# Ethernet.net
KiCad netlist of a schematic drawn in Altium Designer
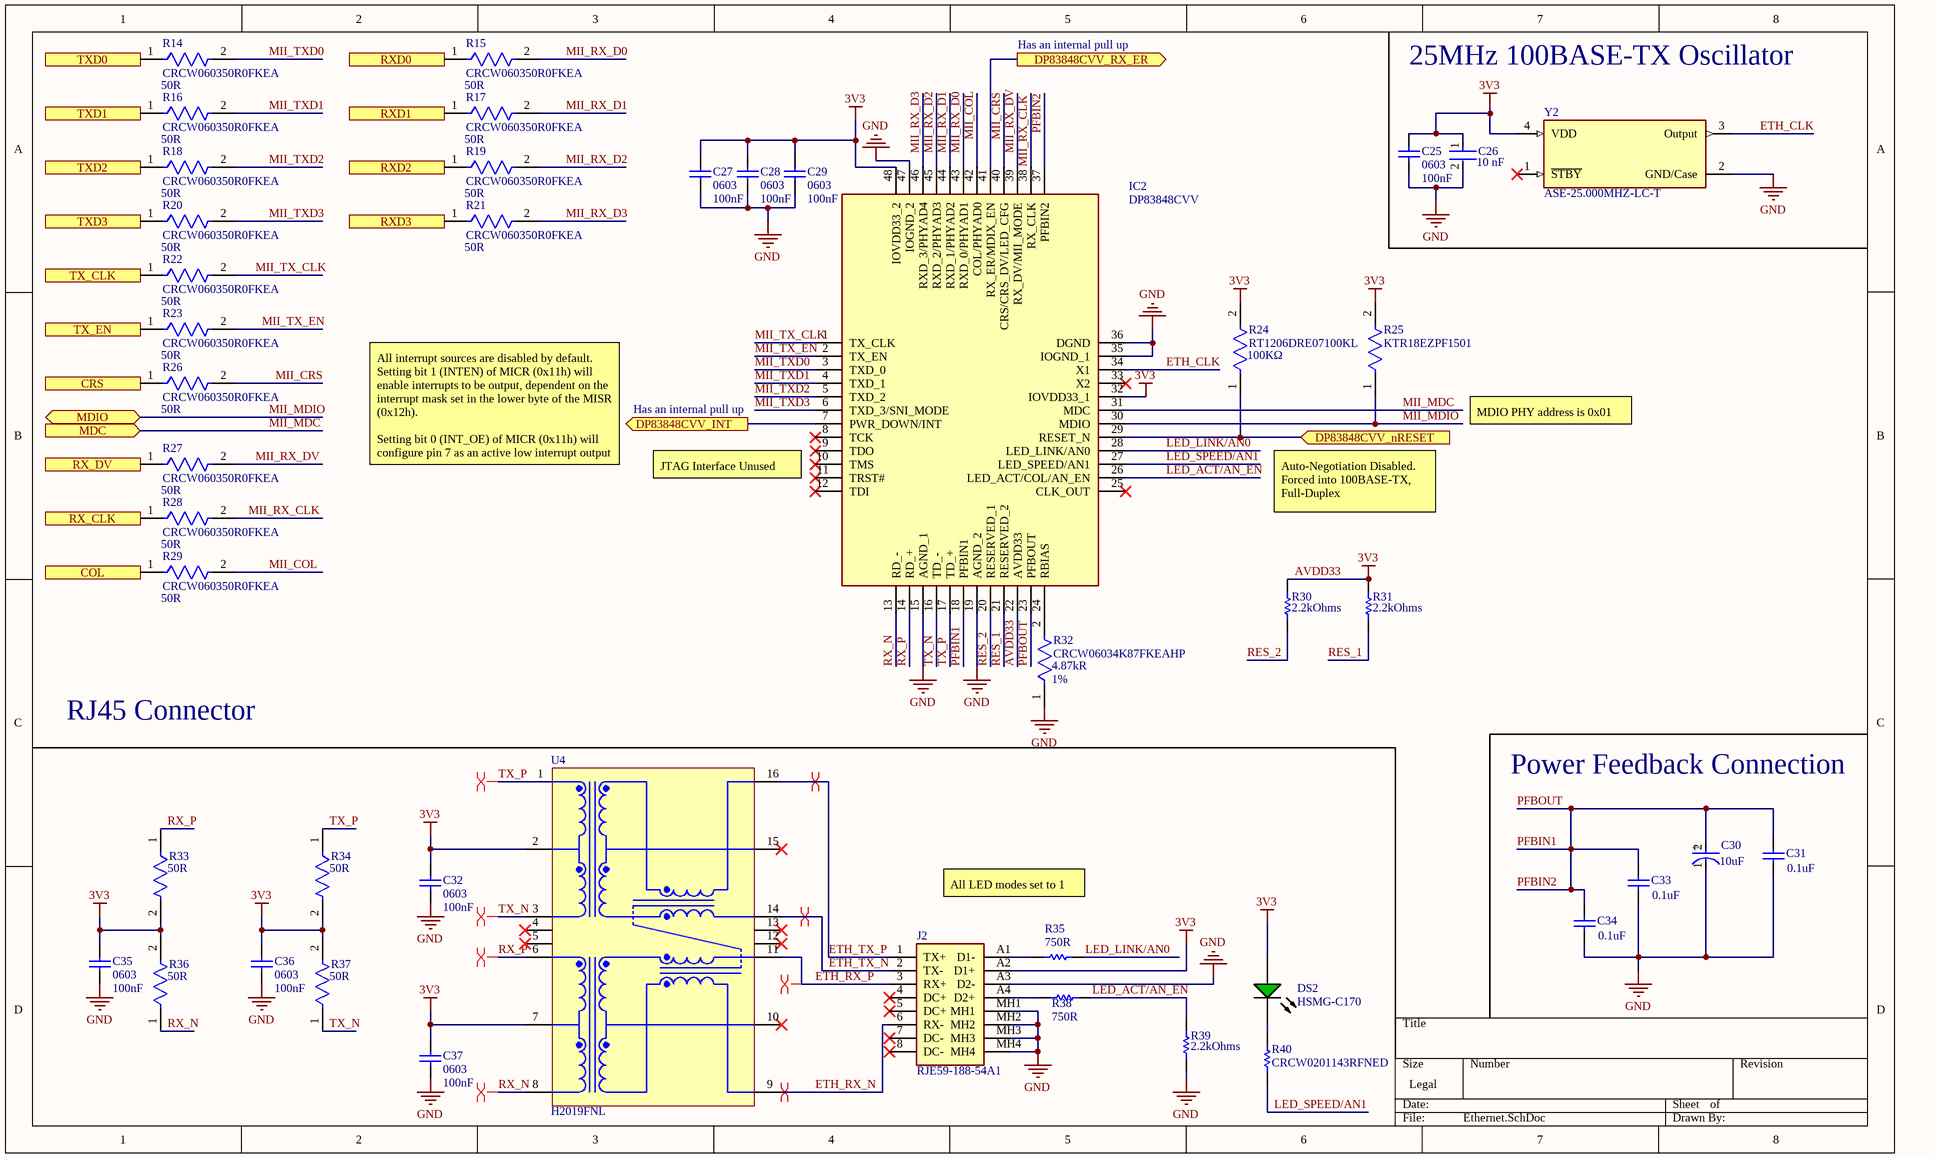
[diagram p0: Ethernet.SchDoc]

(export (version "E")
  (design (tool "Eeschema 10.0.6"))
  (components
    (comp (ref "C25")
      (value "C0603X104K5RACTU")
      (footprint "CAPC1608X87X35NL15T15")
      (fields
        (field (name "MANUFACTURER") "Kemet")
        (field (name "CASE CODE (IMPERIAL)") "0603")
        (field (name "CAPACITANCE") "100nF")
        (field (name "TOLERANCE") "10%")
        (field (name "VOLTAGE") "50V")
      )
      (libsource (lib "Altium Content Vault") (part "CAP"))
    )
    (comp (ref "C26")
      (value "10 nF")
      (footprint "FP-CC0603-DA-MFG")
      (description "CAP CER 10000PF 50V X7R 0603")
      (fields (field (name "TOLERANCE") "0.1") (field (name "MANUFACTURER PART NUMBER") "CC0603KRX7R9BB103"))
      (libsource (lib "Altium Content Vault") (part "11868f565c42a9108669ba33697ecf6"))
    )
    (comp (ref "C27")
      (value "C0603X104K5RACTU")
      (footprint "CAPC1608X87X35NL15T15")
      (fields
        (field (name "MANUFACTURER") "Kemet")
        (field (name "CASE CODE (IMPERIAL)") "0603")
        (field (name "CAPACITANCE") "100nF")
        (field (name "TOLERANCE") "10%")
        (field (name "VOLTAGE") "50V")
      )
      (libsource (lib "Altium Content Vault") (part "CAP"))
    )
    (comp (ref "C28")
      (value "C0603X104K5RACTU")
      (footprint "CAPC1608X87X35NL15T15")
      (fields
        (field (name "MANUFACTURER") "Kemet")
        (field (name "CASE CODE (IMPERIAL)") "0603")
        (field (name "CAPACITANCE") "100nF")
        (field (name "TOLERANCE") "10%")
        (field (name "VOLTAGE") "50V")
      )
      (libsource (lib "Altium Content Vault") (part "CAP"))
    )
    (comp (ref "C29")
      (value "C0603X104K5RACTU")
      (footprint "CAPC1608X87X35NL15T15")
      (fields
        (field (name "MANUFACTURER") "Kemet")
        (field (name "CASE CODE (IMPERIAL)") "0603")
        (field (name "CAPACITANCE") "100nF")
        (field (name "TOLERANCE") "10%")
        (field (name "VOLTAGE") "50V")
      )
      (libsource (lib "Altium Content Vault") (part "CAP"))
    )
    (comp (ref "C30")
      (value "T491B106K025AT")
      (footprint "FP-T491B106K025AT-MFG")
      (description "CAP TANT 10UF 10% 25V 1411")
      (fields
        (field (name "VOLTAGE") "25V")
        (field (name "TOLERANCE") "10%")
        (field (name "CAPACITANCE") "10uF")
      )
      (libsource (lib "Altium Content Vault") (part "a00bbbee19879c290e62620ae7e47b1"))
    )
    (comp (ref "C31")
      (value "0.1uF")
      (footprint "CAPC2113X120X50NL20T30")
      (fields
        (field (name "MANUFACTURER") "AVX Interconnect / Elco")
        (field (name "PART NUMBER") "TAJR104K020RNJ")
      )
      (libsource (lib "Altium Content Vault") (part "CAP"))
    )
    (comp (ref "C32")
      (value "C0603X104K5RACTU")
      (footprint "CAPC1608X87X35NL15T15")
      (fields
        (field (name "MANUFACTURER") "Kemet")
        (field (name "CASE CODE (IMPERIAL)") "0603")
        (field (name "CAPACITANCE") "100nF")
        (field (name "TOLERANCE") "10%")
        (field (name "VOLTAGE") "50V")
      )
      (libsource (lib "Altium Content Vault") (part "CAP"))
    )
    (comp (ref "C33")
      (value "0.1uF")
      (footprint "CAPC2113X120X50NL20T30")
      (fields
        (field (name "MANUFACTURER") "AVX Interconnect / Elco")
        (field (name "PART NUMBER") "TAJR104K020RNJ")
      )
      (libsource (lib "Altium Content Vault") (part "CAP"))
    )
    (comp (ref "C34")
      (value "0.1uF")
      (footprint "CAPC2113X120X50NL20T30")
      (fields
        (field (name "MANUFACTURER") "AVX Interconnect / Elco")
        (field (name "PART NUMBER") "TAJR104K020RNJ")
      )
      (libsource (lib "Altium Content Vault") (part "CAP"))
    )
    (comp (ref "C35")
      (value "C0603X104K5RACTU")
      (footprint "CAPC1608X87X35NL15T15")
      (fields
        (field (name "MANUFACTURER") "Kemet")
        (field (name "CASE CODE (IMPERIAL)") "0603")
        (field (name "CAPACITANCE") "100nF")
        (field (name "TOLERANCE") "10%")
        (field (name "VOLTAGE") "50V")
      )
      (libsource (lib "Altium Content Vault") (part "CAP"))
    )
    (comp (ref "C36")
      (value "C0603X104K5RACTU")
      (footprint "CAPC1608X87X35NL15T15")
      (fields
        (field (name "MANUFACTURER") "Kemet")
        (field (name "CASE CODE (IMPERIAL)") "0603")
        (field (name "CAPACITANCE") "100nF")
        (field (name "TOLERANCE") "10%")
        (field (name "VOLTAGE") "50V")
      )
      (libsource (lib "Altium Content Vault") (part "CAP"))
    )
    (comp (ref "C37")
      (value "C0603X104K5RACTU")
      (footprint "CAPC1608X87X35NL15T15")
      (fields
        (field (name "MANUFACTURER") "Kemet")
        (field (name "CASE CODE (IMPERIAL)") "0603")
        (field (name "CAPACITANCE") "100nF")
        (field (name "TOLERANCE") "10%")
        (field (name "VOLTAGE") "50V")
      )
      (libsource (lib "Altium Content Vault") (part "CAP"))
    )
    (comp (ref "DS2")
      (value "HSMG-C170")
      (footprint "AVAG-HSMX-C170_V")
      (description "Chip LED, Green, 2.2 V, -40 to 85 degC, 2-Pin SMD, Pb-Free, Tape and Reel")
      (fields (field (name "MANUFACTURER") "Avago"))
      (libsource (lib "Altium Content Vault") (part "LED_GREEN_A1K2-2"))
    )
    (comp (ref "IC2")
      (value "DP83848CVV")
      (footprint "SamacSys:QFP50P900X900X160-48N")
      (description "Integrated Circuit")
      (libsource (lib "*") (part "DP83848CVV"))
    )
    (comp (ref "J2")
      (value "RJE59-188-54A1")
      (footprint "SamacSys:RJE5918854A1")
      (description "Connector")
      (fields (field (name "MOUSER PART NUMBER") "523-RJE59-188-54A1"))
      (libsource (lib "*") (part "RJE59-188-54A1"))
    )
    (comp (ref "R14")
      (value "CRCW060350R0FKEA")
      (footprint "FP-CRCW0603-e3-MFG")
      (description "RES Thick Film, 50Ω, 1%, 0.1W, 100ppm/°C, 0603")
      (fields (field (name "TOLERANCE") "1%") (field (name "RESISTANCE") "50R"))
      (libsource (lib "Altium Content Vault") (part "1029c3af85768c4190bb7ad29bc67b5"))
    )
    (comp (ref "R15")
      (value "CRCW060350R0FKEA")
      (footprint "FP-CRCW0603-e3-MFG")
      (description "RES Thick Film, 50Ω, 1%, 0.1W, 100ppm/°C, 0603")
      (fields (field (name "TOLERANCE") "1%") (field (name "RESISTANCE") "50R"))
      (libsource (lib "Altium Content Vault") (part "1029c3af85768c4190bb7ad29bc67b5"))
    )
    (comp (ref "R16")
      (value "CRCW060350R0FKEA")
      (footprint "FP-CRCW0603-e3-MFG")
      (description "RES Thick Film, 50Ω, 1%, 0.1W, 100ppm/°C, 0603")
      (fields (field (name "TOLERANCE") "1%") (field (name "RESISTANCE") "50R"))
      (libsource (lib "Altium Content Vault") (part "1029c3af85768c4190bb7ad29bc67b5"))
    )
    (comp (ref "R17")
      (value "CRCW060350R0FKEA")
      (footprint "FP-CRCW0603-e3-MFG")
      (description "RES Thick Film, 50Ω, 1%, 0.1W, 100ppm/°C, 0603")
      (fields (field (name "TOLERANCE") "1%") (field (name "RESISTANCE") "50R"))
      (libsource (lib "Altium Content Vault") (part "1029c3af85768c4190bb7ad29bc67b5"))
    )
    (comp (ref "R18")
      (value "CRCW060350R0FKEA")
      (footprint "FP-CRCW0603-e3-MFG")
      (description "RES Thick Film, 50Ω, 1%, 0.1W, 100ppm/°C, 0603")
      (fields (field (name "TOLERANCE") "1%") (field (name "RESISTANCE") "50R"))
      (libsource (lib "Altium Content Vault") (part "1029c3af85768c4190bb7ad29bc67b5"))
    )
    (comp (ref "R19")
      (value "CRCW060350R0FKEA")
      (footprint "FP-CRCW0603-e3-MFG")
      (description "RES Thick Film, 50Ω, 1%, 0.1W, 100ppm/°C, 0603")
      (fields (field (name "TOLERANCE") "1%") (field (name "RESISTANCE") "50R"))
      (libsource (lib "Altium Content Vault") (part "1029c3af85768c4190bb7ad29bc67b5"))
    )
    (comp (ref "R20")
      (value "CRCW060350R0FKEA")
      (footprint "FP-CRCW0603-e3-MFG")
      (description "RES Thick Film, 50Ω, 1%, 0.1W, 100ppm/°C, 0603")
      (fields (field (name "TOLERANCE") "1%") (field (name "RESISTANCE") "50R"))
      (libsource (lib "Altium Content Vault") (part "1029c3af85768c4190bb7ad29bc67b5"))
    )
    (comp (ref "R21")
      (value "CRCW060350R0FKEA")
      (footprint "FP-CRCW0603-e3-MFG")
      (description "RES Thick Film, 50Ω, 1%, 0.1W, 100ppm/°C, 0603")
      (fields (field (name "TOLERANCE") "1%") (field (name "RESISTANCE") "50R"))
      (libsource (lib "Altium Content Vault") (part "1029c3af85768c4190bb7ad29bc67b5"))
    )
    (comp (ref "R22")
      (value "CRCW060350R0FKEA")
      (footprint "FP-CRCW0603-e3-MFG")
      (description "RES Thick Film, 50Ω, 1%, 0.1W, 100ppm/°C, 0603")
      (fields (field (name "TOLERANCE") "1%") (field (name "RESISTANCE") "50R"))
      (libsource (lib "Altium Content Vault") (part "1029c3af85768c4190bb7ad29bc67b5"))
    )
    (comp (ref "R23")
      (value "CRCW060350R0FKEA")
      (footprint "FP-CRCW0603-e3-MFG")
      (description "RES Thick Film, 50Ω, 1%, 0.1W, 100ppm/°C, 0603")
      (fields (field (name "TOLERANCE") "1%") (field (name "RESISTANCE") "50R"))
      (libsource (lib "Altium Content Vault") (part "1029c3af85768c4190bb7ad29bc67b5"))
    )
    (comp (ref "R24")
      (value "RT1206DRE07100KL")
      (footprint "FP-RT1206-MFG")
      (description "RES SMD 100K OHM 0.5% 1/4W 1206")
      (fields
        (field (name "MANUFACTURER") "Yageo")
        (field (name "OCTOPART") "https://octopart.com/rt1206dre07100kl-yageo-1189867")
        (field (name "RESISTANCE") "100KΩ")
      )
      (libsource (lib "Altium Content Vault") (part "1029c3af85768c4190bb7ad29bc67b5"))
    )
    (comp (ref "R25")
      (value "KTR18EZPF1501")
      (footprint "FP-KTR18-IPC_C")
      (description "Res Thick Film 1206 1.5kΩ 1% 0.1W ±100ppm/°C Automotive Paper T/R")
      (fields (field (name "TOLERANCE") "1%"))
      (libsource (lib "Altium Content Vault") (part "1029c3af85768c4190bb7ad29bc67b5"))
    )
    (comp (ref "R26")
      (value "CRCW060350R0FKEA")
      (footprint "FP-CRCW0603-e3-MFG")
      (description "RES Thick Film, 50Ω, 1%, 0.1W, 100ppm/°C, 0603")
      (fields (field (name "TOLERANCE") "1%") (field (name "RESISTANCE") "50R"))
      (libsource (lib "Altium Content Vault") (part "1029c3af85768c4190bb7ad29bc67b5"))
    )
    (comp (ref "R27")
      (value "CRCW060350R0FKEA")
      (footprint "FP-CRCW0603-e3-MFG")
      (description "RES Thick Film, 50Ω, 1%, 0.1W, 100ppm/°C, 0603")
      (fields (field (name "TOLERANCE") "1%") (field (name "RESISTANCE") "50R"))
      (libsource (lib "Altium Content Vault") (part "1029c3af85768c4190bb7ad29bc67b5"))
    )
    (comp (ref "R28")
      (value "CRCW060350R0FKEA")
      (footprint "FP-CRCW0603-e3-MFG")
      (description "RES Thick Film, 50Ω, 1%, 0.1W, 100ppm/°C, 0603")
      (fields (field (name "TOLERANCE") "1%") (field (name "RESISTANCE") "50R"))
      (libsource (lib "Altium Content Vault") (part "1029c3af85768c4190bb7ad29bc67b5"))
    )
    (comp (ref "R29")
      (value "CRCW060350R0FKEA")
      (footprint "FP-CRCW0603-e3-MFG")
      (description "RES Thick Film, 50Ω, 1%, 0.1W, 100ppm/°C, 0603")
      (fields (field (name "TOLERANCE") "1%") (field (name "RESISTANCE") "50R"))
      (libsource (lib "Altium Content Vault") (part "1029c3af85768c4190bb7ad29bc67b5"))
    )
    (comp (ref "R30")
      (value "RC0603FR-072K2L")
      (footprint "RESC1608X55X25LL10T15")
      (fields
        (field (name "TOLERANCE") "1%")
        (field (name "RESISTANCE") "2.2kOhms")
        (field (name "MANUFACTURER") "Yageo")
      )
      (libsource (lib "Altium Content Vault") (part "RES-2"))
    )
    (comp (ref "R31")
      (value "RC0603FR-072K2L")
      (footprint "RESC1608X55X25LL10T15")
      (fields
        (field (name "TOLERANCE") "1%")
        (field (name "RESISTANCE") "2.2kOhms")
        (field (name "MANUFACTURER") "Yageo")
      )
      (libsource (lib "Altium Content Vault") (part "RES-2"))
    )
    (comp (ref "R32")
      (value "CRCW06034K87FKEAHP")
      (footprint "FP-CRCW0603-HPe3-MFG")
      (description "RES Thick Film, 4.87kΩ, 1%, 0.33W, 100ppm/°C, 0603")
      (fields (field (name "TOLERANCE") "1%") (field (name "RESISTANCE") "4.87kR"))
      (libsource (lib "Altium Content Vault") (part "1029c3af85768c4190bb7ad29bc67b5"))
    )
    (comp (ref "R33")
      (value "CRCW060350R0FKEA")
      (footprint "FP-CRCW0603-e3-MFG")
      (description "RES Thick Film, 50Ω, 1%, 0.1W, 100ppm/°C, 0603")
      (fields (field (name "TOLERANCE") "1%") (field (name "RESISTANCE") "50R"))
      (libsource (lib "Altium Content Vault") (part "1029c3af85768c4190bb7ad29bc67b5"))
    )
    (comp (ref "R34")
      (value "CRCW060350R0FKEA")
      (footprint "FP-CRCW0603-e3-MFG")
      (description "RES Thick Film, 50Ω, 1%, 0.1W, 100ppm/°C, 0603")
      (fields (field (name "TOLERANCE") "1%") (field (name "RESISTANCE") "50R"))
      (libsource (lib "Altium Content Vault") (part "1029c3af85768c4190bb7ad29bc67b5"))
    )
    (comp (ref "R35")
      (value "CRCW0603750RJNEA")
      (footprint "RESC1609X50X30ML10T20")
      (fields (field (name "MANUFACTURER") "Vishay Dale") (field (name "RESISTANCE") "750R"))
      (libsource (lib "Altium Content Vault") (part "RES"))
    )
    (comp (ref "R36")
      (value "CRCW060350R0FKEA")
      (footprint "FP-CRCW0603-e3-MFG")
      (description "RES Thick Film, 50Ω, 1%, 0.1W, 100ppm/°C, 0603")
      (fields (field (name "TOLERANCE") "1%") (field (name "RESISTANCE") "50R"))
      (libsource (lib "Altium Content Vault") (part "1029c3af85768c4190bb7ad29bc67b5"))
    )
    (comp (ref "R37")
      (value "CRCW060350R0FKEA")
      (footprint "FP-CRCW0603-e3-MFG")
      (description "RES Thick Film, 50Ω, 1%, 0.1W, 100ppm/°C, 0603")
      (fields (field (name "TOLERANCE") "1%") (field (name "RESISTANCE") "50R"))
      (libsource (lib "Altium Content Vault") (part "1029c3af85768c4190bb7ad29bc67b5"))
    )
    (comp (ref "R38")
      (value "CRCW0603750RJNEA")
      (footprint "RESC1609X50X30ML10T20")
      (fields (field (name "MANUFACTURER") "Vishay Dale") (field (name "RESISTANCE") "750R"))
      (libsource (lib "Altium Content Vault") (part "RES"))
    )
    (comp (ref "R39")
      (value "RC0603FR-072K2L")
      (footprint "RESC1608X55X25LL10T15")
      (fields
        (field (name "TOLERANCE") "1%")
        (field (name "RESISTANCE") "2.2kOhms")
        (field (name "MANUFACTURER") "Yageo")
      )
      (libsource (lib "Altium Content Vault") (part "RES-2"))
    )
    (comp (ref "R40")
      (value "CRCW0201143RFNED")
      (footprint "RESC0603X28X15ML05T05")
      (fields (field (name "MANUFACTURER") "Vishay Dale"))
      (libsource (lib "Altium Content Vault") (part "RES"))
    )
    (comp (ref "U4")
      (value "H2019FNL")
      (footprint "PULS-H2019FNL_V")
      (description "Telecom Transformer, 100BASE-TX, 0 to 70 degC, 16-Pin SMD, RoHS")
      (fields (field (name "MANUFACTURER") "Pulse Electronics"))
      (libsource (lib "Altium Content Vault") (part "PULS-H2019FNL-16"))
    )
    (comp (ref "Y2")
      (value "ASE-25.000MHZ-LC-T")
      (footprint "FP-ASE-MFG")
      (description "XTAL Oscillator 25MHz ±50ppm CMOS 3.3V 4-SMD 3.2mm x 2.5mm")
      (libsource (lib "Altium Content Vault") (part "61a724e6190563596ac712fef61ad37"))
    )
  )
  (nets
    (net (code "1") (name "/COL") (class "Default")
      (node (ref "R29") (pin "1") (pinfunction "1_1") (pintype "passive"))
    )
    (net (code "2") (name "/CRS") (class "Default")
      (node (ref "R26") (pin "1") (pinfunction "1_1") (pintype "passive"))
    )
    (net (code "3") (name "/DP83848CVV_INT") (class "Default")
      (node (ref "IC2") (pin "7") (pinfunction "PWR_DOWN/INT_7") (pintype "passive"))
    )
    (net (code "4") (name "/DP83848CVV_RX_ER") (class "Default")
      (node (ref "IC2") (pin "41") (pinfunction "RX_ER/MDIX_EN_41") (pintype "passive"))
    )
    (net (code "5") (name "/DP83848CVV_nRESET") (class "Default")
      (node (ref "IC2") (pin "29") (pinfunction "RESET_N_29") (pintype "passive"))
      (node (ref "R24") (pin "1") (pinfunction "1_1") (pintype "passive"))
    )
    (net (code "6") (name "/ETH_CLK") (class "Default")
      (node (ref "IC2") (pin "34") (pinfunction "X1_34") (pintype "passive"))
      (node (ref "Y2") (pin "3") (pinfunction "Output_3") (pintype "output"))
    )
    (net (code "7") (name "/ETH_RX_N") (class "Default")
      (node (ref "J2") (pin "6") (pinfunction "RX-_6") (pintype "passive"))
      (node (ref "U4") (pin "9") (pinfunction "RX-_9") (pintype "passive"))
    )
    (net (code "8") (name "/ETH_RX_P") (class "Default")
      (node (ref "J2") (pin "3") (pinfunction "RX+_3") (pintype "passive"))
      (node (ref "U4") (pin "11") (pinfunction "RX+_11") (pintype "passive"))
    )
    (net (code "9") (name "/ETH_TX_N") (class "Default")
      (node (ref "J2") (pin "2") (pinfunction "TX-_2") (pintype "passive"))
      (node (ref "U4") (pin "14") (pinfunction "TX-_14") (pintype "passive"))
    )
    (net (code "10") (name "/ETH_TX_P") (class "Default")
      (node (ref "J2") (pin "1") (pinfunction "TX+_1") (pintype "passive"))
      (node (ref "U4") (pin "16") (pinfunction "TX+_16") (pintype "passive"))
    )
    (net (code "11") (name "/LED_ACT{slash}AN_EN") (class "Default")
      (node (ref "IC2") (pin "26") (pinfunction "LED_ACT/COL/AN_EN_26") (pintype "passive"))
      (node (ref "R38") (pin "2") (pinfunction "2_2") (pintype "passive"))
      (node (ref "R39") (pin "2") (pinfunction "2_2") (pintype "passive"))
    )
    (net (code "12") (name "/LED_LINK{slash}AN0") (class "Default")
      (node (ref "IC2") (pin "28") (pinfunction "LED_LINK/AN0_28") (pintype "passive"))
      (node (ref "R35") (pin "2") (pinfunction "2_2") (pintype "passive"))
    )
    (net (code "13") (name "/LED_SPEED{slash}AN1") (class "Default")
      (node (ref "IC2") (pin "27") (pinfunction "LED_SPEED/AN1_27") (pintype "passive"))
      (node (ref "R40") (pin "1") (pinfunction "1_1") (pintype "passive"))
    )
    (net (code "14") (name "/MII_COL") (class "Default")
      (node (ref "IC2") (pin "42") (pinfunction "COL/PHYAD0_42") (pintype "passive"))
      (node (ref "R29") (pin "2") (pinfunction "2_2") (pintype "passive"))
    )
    (net (code "15") (name "/MII_CRS") (class "Default")
      (node (ref "IC2") (pin "40") (pinfunction "CRS/CRS_DV/LED_CFG_40") (pintype "passive"))
      (node (ref "R26") (pin "2") (pinfunction "2_2") (pintype "passive"))
    )
    (net (code "16") (name "/MII_MDC") (class "Default")
      (node (ref "IC2") (pin "31") (pinfunction "MDC_31") (pintype "passive"))
    )
    (net (code "17") (name "/MII_MDIO") (class "Default")
      (node (ref "IC2") (pin "30") (pinfunction "MDIO_30") (pintype "passive"))
      (node (ref "R25") (pin "1") (pinfunction "1_1") (pintype "passive"))
    )
    (net (code "18") (name "/MII_RX_CLK") (class "Default")
      (node (ref "IC2") (pin "38") (pinfunction "RX_CLK_38") (pintype "passive"))
      (node (ref "R28") (pin "2") (pinfunction "2_2") (pintype "passive"))
    )
    (net (code "19") (name "/MII_RX_D0") (class "Default")
      (node (ref "IC2") (pin "43") (pinfunction "RXD_0/PHYAD1_43") (pintype "passive"))
      (node (ref "R15") (pin "2") (pinfunction "2_2") (pintype "passive"))
    )
    (net (code "20") (name "/MII_RX_D1") (class "Default")
      (node (ref "IC2") (pin "44") (pinfunction "RXD_1/PHYAD2_44") (pintype "passive"))
      (node (ref "R17") (pin "2") (pinfunction "2_2") (pintype "passive"))
    )
    (net (code "21") (name "/MII_RX_D2") (class "Default")
      (node (ref "IC2") (pin "45") (pinfunction "RXD_2/PHYAD3_45") (pintype "passive"))
      (node (ref "R19") (pin "2") (pinfunction "2_2") (pintype "passive"))
    )
    (net (code "22") (name "/MII_RX_D3") (class "Default")
      (node (ref "IC2") (pin "46") (pinfunction "RXD_3/PHYAD4_46") (pintype "passive"))
      (node (ref "R21") (pin "2") (pinfunction "2_2") (pintype "passive"))
    )
    (net (code "23") (name "/MII_RX_DV") (class "Default")
      (node (ref "IC2") (pin "39") (pinfunction "RX_DV/MII_MODE_39") (pintype "passive"))
      (node (ref "R27") (pin "2") (pinfunction "2_2") (pintype "passive"))
    )
    (net (code "24") (name "/MII_TXD0") (class "Default")
      (node (ref "IC2") (pin "3") (pinfunction "TXD_0_3") (pintype "passive"))
      (node (ref "R14") (pin "2") (pinfunction "2_2") (pintype "passive"))
    )
    (net (code "25") (name "/MII_TXD1") (class "Default")
      (node (ref "IC2") (pin "4") (pinfunction "TXD_1_4") (pintype "passive"))
      (node (ref "R16") (pin "2") (pinfunction "2_2") (pintype "passive"))
    )
    (net (code "26") (name "/MII_TXD2") (class "Default")
      (node (ref "IC2") (pin "5") (pinfunction "TXD_2_5") (pintype "passive"))
      (node (ref "R18") (pin "2") (pinfunction "2_2") (pintype "passive"))
    )
    (net (code "27") (name "/MII_TXD3") (class "Default")
      (node (ref "IC2") (pin "6") (pinfunction "TXD_3/SNI_MODE_6") (pintype "passive"))
      (node (ref "R20") (pin "2") (pinfunction "2_2") (pintype "passive"))
    )
    (net (code "28") (name "/MII_TX_CLK") (class "Default")
      (node (ref "IC2") (pin "1") (pinfunction "TX_CLK_1") (pintype "passive"))
      (node (ref "R22") (pin "2") (pinfunction "2_2") (pintype "passive"))
    )
    (net (code "29") (name "/MII_TX_EN") (class "Default")
      (node (ref "IC2") (pin "2") (pinfunction "TX_EN_2") (pintype "passive"))
      (node (ref "R23") (pin "2") (pinfunction "2_2") (pintype "passive"))
    )
    (net (code "30") (name "/PFBIN1") (class "Default")
      (node (ref "C30") (pin "2") (pinfunction "A_2") (pintype "passive"))
      (node (ref "C31") (pin "2") (pinfunction "2_2") (pintype "passive"))
      (node (ref "C33") (pin "2") (pinfunction "2_2") (pintype "passive"))
      (node (ref "C34") (pin "2") (pinfunction "2_2") (pintype "passive"))
      (node (ref "IC2") (pin "18") (pinfunction "PFBIN1_18") (pintype "passive"))
      (node (ref "IC2") (pin "23") (pinfunction "PFBOUT_23") (pintype "passive"))
      (node (ref "IC2") (pin "37") (pinfunction "PFBIN2_37") (pintype "passive"))
    )
    (net (code "31") (name "/RES_1") (class "Default")
      (node (ref "IC2") (pin "21") (pinfunction "RESERVED_2_21") (pintype "passive"))
      (node (ref "R31") (pin "1") (pinfunction "1_1") (pintype "passive"))
    )
    (net (code "32") (name "/RES_2") (class "Default")
      (node (ref "IC2") (pin "20") (pinfunction "RESERVED_1_20") (pintype "passive"))
      (node (ref "R30") (pin "1") (pinfunction "1_1") (pintype "passive"))
    )
    (net (code "33") (name "/RXD0") (class "Default")
      (node (ref "R15") (pin "1") (pinfunction "1_1") (pintype "passive"))
    )
    (net (code "34") (name "/RXD1") (class "Default")
      (node (ref "R17") (pin "1") (pinfunction "1_1") (pintype "passive"))
    )
    (net (code "35") (name "/RXD2") (class "Default")
      (node (ref "R19") (pin "1") (pinfunction "1_1") (pintype "passive"))
    )
    (net (code "36") (name "/RXD3") (class "Default")
      (node (ref "R21") (pin "1") (pinfunction "1_1") (pintype "passive"))
    )
    (net (code "37") (name "/RX_CLK") (class "Default")
      (node (ref "R28") (pin "1") (pinfunction "1_1") (pintype "passive"))
    )
    (net (code "38") (name "/RX_DV") (class "Default")
      (node (ref "R27") (pin "1") (pinfunction "1_1") (pintype "passive"))
    )
    (net (code "39") (name "/RX_N") (class "Default")
      (node (ref "IC2") (pin "13") (pinfunction "RD_-_13") (pintype "passive"))
      (node (ref "R36") (pin "1") (pinfunction "1_1") (pintype "passive"))
      (node (ref "U4") (pin "8") (pinfunction "RD-_8") (pintype "passive"))
    )
    (net (code "40") (name "/RX_P") (class "Default")
      (node (ref "IC2") (pin "14") (pinfunction "RD_+_14") (pintype "passive"))
      (node (ref "R33") (pin "1") (pinfunction "1_1") (pintype "passive"))
      (node (ref "U4") (pin "6") (pinfunction "RD+_6") (pintype "passive"))
    )
    (net (code "41") (name "/TXD0") (class "Default")
      (node (ref "R14") (pin "1") (pinfunction "1_1") (pintype "passive"))
    )
    (net (code "42") (name "/TXD1") (class "Default")
      (node (ref "R16") (pin "1") (pinfunction "1_1") (pintype "passive"))
    )
    (net (code "43") (name "/TXD2") (class "Default")
      (node (ref "R18") (pin "1") (pinfunction "1_1") (pintype "passive"))
    )
    (net (code "44") (name "/TXD3") (class "Default")
      (node (ref "R20") (pin "1") (pinfunction "1_1") (pintype "passive"))
    )
    (net (code "45") (name "/TX_CLK") (class "Default")
      (node (ref "R22") (pin "1") (pinfunction "1_1") (pintype "passive"))
    )
    (net (code "46") (name "/TX_EN") (class "Default")
      (node (ref "R23") (pin "1") (pinfunction "1_1") (pintype "passive"))
    )
    (net (code "47") (name "/TX_N") (class "Default")
      (node (ref "IC2") (pin "16") (pinfunction "TD_-_16") (pintype "passive"))
      (node (ref "R37") (pin "1") (pinfunction "1_1") (pintype "passive"))
      (node (ref "U4") (pin "3") (pinfunction "TD-_3") (pintype "passive"))
    )
    (net (code "48") (name "/TX_P") (class "Default")
      (node (ref "IC2") (pin "17") (pinfunction "TD_+_17") (pintype "passive"))
      (node (ref "R34") (pin "1") (pinfunction "1_1") (pintype "passive"))
      (node (ref "U4") (pin "1") (pinfunction "TD+_1") (pintype "passive"))
    )
    (net (code "49") (name "3V3") (class "Default")
      (node (ref "C25") (pin "1") (pinfunction "1_1") (pintype "passive"))
      (node (ref "C26") (pin "1") (pinfunction "1_1") (pintype "passive"))
      (node (ref "C27") (pin "1") (pinfunction "1_1") (pintype "passive"))
      (node (ref "C28") (pin "1") (pinfunction "1_1") (pintype "passive"))
      (node (ref "C29") (pin "1") (pinfunction "1_1") (pintype "passive"))
      (node (ref "C32") (pin "1") (pinfunction "1_1") (pintype "passive"))
      (node (ref "C35") (pin "1") (pinfunction "1_1") (pintype "passive"))
      (node (ref "C36") (pin "1") (pinfunction "1_1") (pintype "passive"))
      (node (ref "C37") (pin "1") (pinfunction "1_1") (pintype "passive"))
      (node (ref "DS2") (pin "1") (pinfunction "A_1") (pintype "passive"))
      (node (ref "IC2") (pin "22") (pinfunction "AVDD33_22") (pintype "passive"))
      (node (ref "IC2") (pin "32") (pinfunction "IOVDD33_1_32") (pintype "passive"))
      (node (ref "IC2") (pin "48") (pinfunction "IOVDD33_2_48") (pintype "passive"))
      (node (ref "J2") (pin "A2") (pinfunction "D1+_A2") (pintype "passive"))
      (node (ref "R24") (pin "2") (pinfunction "2_2") (pintype "passive"))
      (node (ref "R25") (pin "2") (pinfunction "2_2") (pintype "passive"))
      (node (ref "R30") (pin "2") (pinfunction "2_2") (pintype "passive"))
      (node (ref "R31") (pin "2") (pinfunction "2_2") (pintype "passive"))
      (node (ref "R33") (pin "2") (pinfunction "2_2") (pintype "passive"))
      (node (ref "R34") (pin "2") (pinfunction "2_2") (pintype "passive"))
      (node (ref "R36") (pin "2") (pinfunction "2_2") (pintype "passive"))
      (node (ref "R37") (pin "2") (pinfunction "2_2") (pintype "passive"))
      (node (ref "U4") (pin "2") (pinfunction "TCT_2") (pintype "passive"))
      (node (ref "U4") (pin "7") (pinfunction "RCT_7") (pintype "passive"))
      (node (ref "Y2") (pin "4") (pinfunction "VDD_4") (pintype "input"))
    )
    (net (code "50") (name "GND") (class "Default")
      (node (ref "C25") (pin "2") (pinfunction "2_2") (pintype "passive"))
      (node (ref "C26") (pin "2") (pinfunction "2_2") (pintype "passive"))
      (node (ref "C27") (pin "2") (pinfunction "2_2") (pintype "passive"))
      (node (ref "C28") (pin "2") (pinfunction "2_2") (pintype "passive"))
      (node (ref "C29") (pin "2") (pinfunction "2_2") (pintype "passive"))
      (node (ref "C30") (pin "1") (pinfunction "C_1") (pintype "passive"))
      (node (ref "C31") (pin "1") (pinfunction "1_1") (pintype "passive"))
      (node (ref "C32") (pin "2") (pinfunction "2_2") (pintype "passive"))
      (node (ref "C33") (pin "1") (pinfunction "1_1") (pintype "passive"))
      (node (ref "C34") (pin "1") (pinfunction "1_1") (pintype "passive"))
      (node (ref "C35") (pin "2") (pinfunction "2_2") (pintype "passive"))
      (node (ref "C36") (pin "2") (pinfunction "2_2") (pintype "passive"))
      (node (ref "C37") (pin "2") (pinfunction "2_2") (pintype "passive"))
      (node (ref "IC2") (pin "15") (pinfunction "AGND_1_15") (pintype "passive"))
      (node (ref "IC2") (pin "19") (pinfunction "AGND_2_19") (pintype "passive"))
      (node (ref "IC2") (pin "35") (pinfunction "IOGND_1_35") (pintype "passive"))
      (node (ref "IC2") (pin "36") (pinfunction "DGND_36") (pintype "passive"))
      (node (ref "IC2") (pin "47") (pinfunction "IOGND_2_47") (pintype "passive"))
      (node (ref "J2") (pin "A3") (pinfunction "D2-_A3") (pintype "passive"))
      (node (ref "J2") (pin "MH1") (pinfunction "MH1_MH1") (pintype "passive"))
      (node (ref "J2") (pin "MH2") (pinfunction "MH2_MH2") (pintype "passive"))
      (node (ref "J2") (pin "MH3") (pinfunction "MH3_MH3") (pintype "passive"))
      (node (ref "J2") (pin "MH4") (pinfunction "MH4_MH4") (pintype "passive"))
      (node (ref "R32") (pin "1") (pinfunction "1_1") (pintype "passive"))
      (node (ref "R39") (pin "1") (pinfunction "1_1") (pintype "passive"))
      (node (ref "Y2") (pin "2") (pinfunction "GND/Case_2") (pintype "power_in"))
    )
    (net (code "51") (name "Net-(DS2-K)") (class "Default")
      (node (ref "DS2") (pin "2") (pinfunction "K_2") (pintype "passive"))
      (node (ref "R40") (pin "2") (pinfunction "2_2") (pintype "passive"))
    )
    (net (code "52") (name "Net-(IC2-RBIAS)") (class "Default")
      (node (ref "IC2") (pin "24") (pinfunction "RBIAS_24") (pintype "passive"))
      (node (ref "R32") (pin "2") (pinfunction "2_2") (pintype "passive"))
    )
    (net (code "53") (name "Net-(J2-D1-)") (class "Default")
      (node (ref "J2") (pin "A1") (pinfunction "D1-_A1") (pintype "passive"))
      (node (ref "R35") (pin "1") (pinfunction "1_1") (pintype "passive"))
    )
    (net (code "54") (name "Net-(J2-D2+)") (class "Default")
      (node (ref "J2") (pin "A4") (pinfunction "D2+_A4") (pintype "passive"))
      (node (ref "R38") (pin "1") (pinfunction "1_1") (pintype "passive"))
    )
    (net (code "55") (name "unconnected-(IC2-CLK_OUT-Pad25)") (class "Default")
      (node (ref "IC2") (pin "25") (pinfunction "CLK_OUT_25") (pintype "passive+no_connect"))
    )
    (net (code "56") (name "unconnected-(IC2-TCK-Pad8)") (class "Default")
      (node (ref "IC2") (pin "8") (pinfunction "TCK_8") (pintype "passive+no_connect"))
    )
    (net (code "57") (name "unconnected-(IC2-TDI-Pad12)") (class "Default")
      (node (ref "IC2") (pin "12") (pinfunction "TDI_12") (pintype "passive+no_connect"))
    )
    (net (code "58") (name "unconnected-(IC2-TDO-Pad9)") (class "Default")
      (node (ref "IC2") (pin "9") (pinfunction "TDO_9") (pintype "passive+no_connect"))
    )
    (net (code "59") (name "unconnected-(IC2-TMS-Pad10)") (class "Default")
      (node (ref "IC2") (pin "10") (pinfunction "TMS_10") (pintype "passive+no_connect"))
    )
    (net (code "60") (name "unconnected-(IC2-TRST#-Pad11)") (class "Default")
      (node (ref "IC2") (pin "11") (pinfunction "TRST#_11") (pintype "passive+no_connect"))
    )
    (net (code "61") (name "unconnected-(IC2-X2-Pad33)") (class "Default")
      (node (ref "IC2") (pin "33") (pinfunction "X2_33") (pintype "passive+no_connect"))
    )
    (net (code "62") (name "unconnected-(J2-DC+-Pad4)") (class "Default")
      (node (ref "J2") (pin "4") (pinfunction "DC+_4") (pintype "passive+no_connect"))
    )
    (net (code "63") (name "unconnected-(J2-DC+-Pad5)") (class "Default")
      (node (ref "J2") (pin "5") (pinfunction "DC+_5") (pintype "passive+no_connect"))
    )
    (net (code "64") (name "unconnected-(J2-DC--Pad7)") (class "Default")
      (node (ref "J2") (pin "7") (pinfunction "DC-_7") (pintype "passive+no_connect"))
    )
    (net (code "65") (name "unconnected-(J2-DC--Pad8)") (class "Default")
      (node (ref "J2") (pin "8") (pinfunction "DC-_8") (pintype "passive+no_connect"))
    )
    (net (code "66") (name "unconnected-(U4-NC-Pad4)") (class "Default")
      (node (ref "U4") (pin "4") (pinfunction "NC_4") (pintype "passive+no_connect"))
    )
    (net (code "67") (name "unconnected-(U4-NC-Pad5)") (class "Default")
      (node (ref "U4") (pin "5") (pinfunction "NC_5") (pintype "passive+no_connect"))
    )
    (net (code "68") (name "unconnected-(U4-NC-Pad12)") (class "Default")
      (node (ref "U4") (pin "12") (pinfunction "NC_12") (pintype "passive+no_connect"))
    )
    (net (code "69") (name "unconnected-(U4-NC-Pad13)") (class "Default")
      (node (ref "U4") (pin "13") (pinfunction "NC_13") (pintype "passive+no_connect"))
    )
    (net (code "70") (name "unconnected-(U4-RXCT-Pad10)") (class "Default")
      (node (ref "U4") (pin "10") (pinfunction "RXCT_10") (pintype "passive+no_connect"))
    )
    (net (code "71") (name "unconnected-(U4-TXCT-Pad15)") (class "Default")
      (node (ref "U4") (pin "15") (pinfunction "TXCT_15") (pintype "passive+no_connect"))
    )
    (net (code "72") (name "unconnected-(Y2-~{STBY}-Pad1)") (class "Default")
      (node (ref "Y2") (pin "1") (pinfunction "~{STBY}_1") (pintype "input+no_connect"))
    )
  )
)
